# Snickerdoodle_PS.net
KiCad netlist of a schematic drawn in Altium Designer
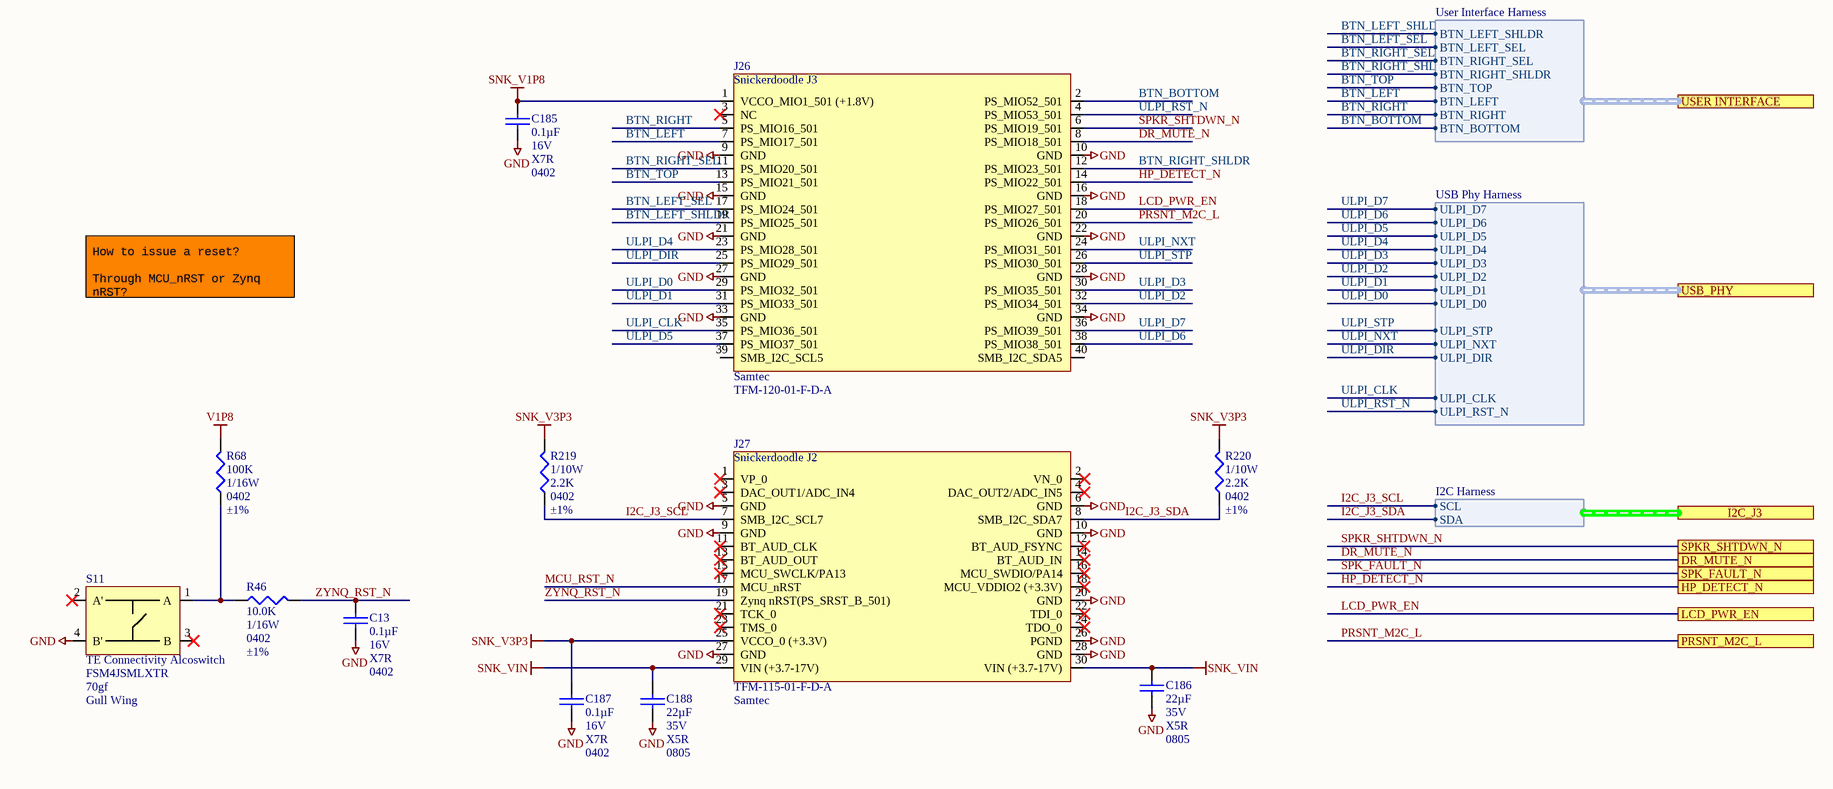
[diagram p0: Snickerdoodle PS.SchDoc]

(export (version "E")
  (design (tool "Eeschema 10.0.6"))
  (components
    (comp (ref "C13")
      (value "0.1uF")
      (footprint "C_0402")
      (description "CAP CER .10UF 16V X7R 0402")
      (fields
        (field (name "MANUFACTURER") "Murata Electronics North America")
        (field (name "MANUFACTURER PART NUMBER") "GRM155R71C104KA88J")
        (field (name "CAPACITANCE") "0.1µF")
        (field (name "VOLTAGE - RATED") "16V")
        (field (name "TEMPERATURE COEFFICIENT") "X7R")
        (field (name "PACKAGE / CASE") "0402")
      )
      (libsource (lib "Main LibraryX") (part "C_0402_0.1UF_16V"))
    )
    (comp (ref "C185")
      (value "0.1uF")
      (footprint "C_0402")
      (description "CAP CER .10UF 16V X7R 0402")
      (fields
        (field (name "MANUFACTURER") "Murata Electronics North America")
        (field (name "MANUFACTURER PART NUMBER") "GRM155R71C104KA88J")
        (field (name "CAPACITANCE") "0.1µF")
        (field (name "VOLTAGE - RATED") "16V")
        (field (name "TEMPERATURE COEFFICIENT") "X7R")
        (field (name "PACKAGE / CASE") "0402")
      )
      (libsource (lib "Main LibraryX") (part "C_0402_0.1UF_16V"))
    )
    (comp (ref "C186")
      (value "C_0805_22µF_35V")
      (footprint "C_ERA-0805")
      (description "CAP CER 22UF 35V X5R 0805")
      (fields
        (field (name "MANUFACTURER") "TDK Corporation")
        (field (name "MANUFACTURER PART NUMBER") "C2012X5R1V226M125AC")
        (field (name "CAPACITANCE") "22µF")
        (field (name "VOLTAGE - RATED") "35V")
        (field (name "TEMPERATURE COEFFICIENT") "X5R")
        (field (name "PACKAGE / CASE") "0805")
      )
      (libsource (lib "Cospan Design") (part "C_0805_22µF_35V"))
    )
    (comp (ref "C187")
      (value "0.1uF")
      (footprint "C_0402")
      (description "CAP CER .10UF 16V X7R 0402")
      (fields
        (field (name "MANUFACTURER") "Murata Electronics North America")
        (field (name "MANUFACTURER PART NUMBER") "GRM155R71C104KA88J")
        (field (name "CAPACITANCE") "0.1µF")
        (field (name "VOLTAGE - RATED") "16V")
        (field (name "TEMPERATURE COEFFICIENT") "X7R")
        (field (name "PACKAGE / CASE") "0402")
      )
      (libsource (lib "Main LibraryX") (part "C_0402_0.1UF_16V"))
    )
    (comp (ref "C188")
      (value "C_0805_22µF_35V")
      (footprint "C_ERA-0805")
      (description "CAP CER 22UF 35V X5R 0805")
      (fields
        (field (name "MANUFACTURER") "TDK Corporation")
        (field (name "MANUFACTURER PART NUMBER") "C2012X5R1V226M125AC")
        (field (name "CAPACITANCE") "22µF")
        (field (name "VOLTAGE - RATED") "35V")
        (field (name "TEMPERATURE COEFFICIENT") "X5R")
        (field (name "PACKAGE / CASE") "0805")
      )
      (libsource (lib "Cospan Design") (part "C_0805_22µF_35V"))
    )
    (comp (ref "J26")
      (value "J_SNICKERDOODLE_J3")
      (footprint "TFM12001-X-D-A")
      (description "SNICKERDOODLE J3")
      (fields
        (field (name "MANUFACTURER") "Samtec")
        (field (name "MANUFACTURER PART NUMBER") "TFM-120-01-F-D-A")
      )
      (libsource (lib "Cospan Design") (part "J_SNICKERDOODLE_J3"))
    )
    (comp (ref "J27")
      (value "J_SNICKERDOODLE_J2")
      (footprint "TFM11501-X-D-A")
      (description "SNICKERDOODLE J2")
      (fields
        (field (name "MANUFACTURER PART NUMBER") "TFM-115-01-F-D-A")
        (field (name "MANUFACTURER") "Samtec")
      )
      (libsource (lib "Cospan Design") (part "J_SNICKERDOODLE_J2"))
    )
    (comp (ref "R46")
      (value "R_0402_10.0K")
      (footprint "R_0402")
      (description "RES 10.0K OHM 1/16W 1% 0402 SMD")
      (fields
        (field (name "MANUFACTURER") "Stackpole Electronics Inc")
        (field (name "MANUFACTURER PART NUMBER") "RMCF0402FT10K0")
        (field (name "RESISTANCE IN OHMS") "10.0K")
        (field (name "POWER (WATTS)") "1/16W")
        (field (name "CASE") "0402")
        (field (name "TOLERANCE") "±1%")
      )
      (libsource (lib "Cospan Design") (part "R_0402_10.0K"))
    )
    (comp (ref "R68")
      (value "R_0402_100K")
      (footprint "R_0402")
      (description "RES SMD 100K OHM 1% 1/16W 0402")
      (fields
        (field (name "MANUFACTURER") "Yageo")
        (field (name "MANUFACTURER PART NUMBER") "RC0402FR-07100KL")
        (field (name "RESISTANCE IN OHMS") "100K")
        (field (name "POWER (WATTS)") "1/16W")
        (field (name "CASE") "0402")
        (field (name "TOLERANCE") "±1%")
      )
      (libsource (lib "Cospan Design") (part "R_0402_100K"))
    )
    (comp (ref "R219")
      (value "2.2k Ohms")
      (footprint "R_0402")
      (description "RES 2.20K OHM 1/10W 1% 0402 SMD")
      (fields
        (field (name "MANUFACTURER") "Yageo")
        (field (name "MANUFACTURER PART NUMBER") "RC0402FR-072K2L")
        (field (name "POWER (WATTS)") "1/10W")
        (field (name "RESISTANCE IN OHMS") "2.2K")
        (field (name "CASE") "0402")
        (field (name "TOLERANCE") "±1%")
      )
      (libsource (lib "Main Library") (part "R_0402_2.2K"))
    )
    (comp (ref "R220")
      (value "2.2k Ohms")
      (footprint "R_0402")
      (description "RES 2.20K OHM 1/10W 1% 0402 SMD")
      (fields
        (field (name "MANUFACTURER") "Yageo")
        (field (name "MANUFACTURER PART NUMBER") "RC0402FR-072K2L")
        (field (name "POWER (WATTS)") "1/10W")
        (field (name "RESISTANCE IN OHMS") "2.2K")
        (field (name "CASE") "0402")
        (field (name "TOLERANCE") "±1%")
      )
      (libsource (lib "Main Library") (part "R_0402_2.2K"))
    )
    (comp (ref "S11")
      (value "S_TACTILE_1571563_2_BUTTON")
      (footprint "TACTILE_1571563_2")
      (description "SWITCH TACTILE SPST-NO 0.05A 24V")
      (fields
        (field (name "MANUFACTURER") "TE Connectivity Alcoswitch")
        (field (name "MANUFACTURER PART NUMBER") "FSM4JSMLXTR")
        (field (name "OPERATING FORCE") "70gf")
        (field (name "TERMINATION") "Gull Wing")
      )
      (libsource (lib "Cospan Design") (part "S_TACTILE_1571563_2_BUTTON"))
    )
  )
  (nets
    (net (code "7") (name "/BTN_BOTTOM") (class "Default")
      (node (ref "J26") (pin "2") (pinfunction "PS_MIO52_501_2") (pintype "passive"))
    )
    (net (code "8") (name "/BTN_LEFT") (class "Default")
      (node (ref "J26") (pin "7") (pinfunction "PS_MIO17_501_7") (pintype "passive"))
    )
    (net (code "9") (name "/BTN_LEFT_SEL") (class "Default")
      (node (ref "J26") (pin "17") (pinfunction "PS_MIO24_501_17") (pintype "passive"))
    )
    (net (code "10") (name "/BTN_LEFT_SHLDR") (class "Default")
      (node (ref "J26") (pin "19") (pinfunction "PS_MIO25_501_19") (pintype "passive"))
    )
    (net (code "11") (name "/BTN_RIGHT") (class "Default")
      (node (ref "J26") (pin "5") (pinfunction "PS_MIO16_501_5") (pintype "passive"))
    )
    (net (code "12") (name "/BTN_RIGHT_SEL") (class "Default")
      (node (ref "J26") (pin "11") (pinfunction "PS_MIO20_501_11") (pintype "passive"))
    )
    (net (code "13") (name "/BTN_RIGHT_SHLDR") (class "Default")
      (node (ref "J26") (pin "12") (pinfunction "PS_MIO23_501_12") (pintype "passive"))
    )
    (net (code "14") (name "/BTN_TOP") (class "Default")
      (node (ref "J26") (pin "13") (pinfunction "PS_MIO21_501_13") (pintype "passive"))
    )
    (net (code "15") (name "/DR_MUTE_N") (class "Default")
      (node (ref "J26") (pin "8") (pinfunction "PS_MIO18_501_8") (pintype "passive"))
    )
    (net (code "16") (name "/HP_DETECT_N") (class "Default")
      (node (ref "J26") (pin "14") (pinfunction "PS_MIO22_501_14") (pintype "passive"))
    )
    (net (code "17") (name "/I2C_J3_SCL") (class "Default")
      (node (ref "J27") (pin "7") (pinfunction "SMB_I2C_SCL7_7") (pintype "passive"))
      (node (ref "R219") (pin "2") (pinfunction "2_2") (pintype "passive"))
    )
    (net (code "18") (name "/I2C_J3_SDA") (class "Default")
      (node (ref "J27") (pin "8") (pinfunction "SMB_I2C_SDA7_8") (pintype "passive"))
      (node (ref "R220") (pin "2") (pinfunction "2_2") (pintype "passive"))
    )
    (net (code "19") (name "/LCD_PWR_EN") (class "Default")
      (node (ref "J26") (pin "18") (pinfunction "PS_MIO27_501_18") (pintype "passive"))
    )
    (net (code "20") (name "/MCU_RST_N") (class "Default")
      (node (ref "J27") (pin "17") (pinfunction "MCU_nRST_17") (pintype "passive"))
    )
    (net (code "21") (name "/PRSNT_M2C_L") (class "Default")
      (node (ref "J26") (pin "20") (pinfunction "PS_MIO26_501_20") (pintype "passive"))
    )
    (net (code "22") (name "/SPKR_SHTDWN_N") (class "Default")
      (node (ref "J26") (pin "6") (pinfunction "PS_MIO19_501_6") (pintype "passive"))
    )
    (net (code "24") (name "/ULPI_CLK") (class "Default")
      (node (ref "J26") (pin "35") (pinfunction "PS_MIO36_501_35") (pintype "passive"))
    )
    (net (code "25") (name "/ULPI_D0") (class "Default")
      (node (ref "J26") (pin "29") (pinfunction "PS_MIO32_501_29") (pintype "passive"))
    )
    (net (code "26") (name "/ULPI_D1") (class "Default")
      (node (ref "J26") (pin "31") (pinfunction "PS_MIO33_501_31") (pintype "passive"))
    )
    (net (code "27") (name "/ULPI_D2") (class "Default")
      (node (ref "J26") (pin "32") (pinfunction "PS_MIO34_501_32") (pintype "passive"))
    )
    (net (code "28") (name "/ULPI_D3") (class "Default")
      (node (ref "J26") (pin "30") (pinfunction "PS_MIO35_501_30") (pintype "passive"))
    )
    (net (code "29") (name "/ULPI_D4") (class "Default")
      (node (ref "J26") (pin "23") (pinfunction "PS_MIO28_501_23") (pintype "passive"))
    )
    (net (code "30") (name "/ULPI_D5") (class "Default")
      (node (ref "J26") (pin "37") (pinfunction "PS_MIO37_501_37") (pintype "passive"))
    )
    (net (code "31") (name "/ULPI_D6") (class "Default")
      (node (ref "J26") (pin "38") (pinfunction "PS_MIO38_501_38") (pintype "passive"))
    )
    (net (code "32") (name "/ULPI_D7") (class "Default")
      (node (ref "J26") (pin "36") (pinfunction "PS_MIO39_501_36") (pintype "passive"))
    )
    (net (code "33") (name "/ULPI_DIR") (class "Default")
      (node (ref "J26") (pin "25") (pinfunction "PS_MIO29_501_25") (pintype "passive"))
    )
    (net (code "34") (name "/ULPI_NXT") (class "Default")
      (node (ref "J26") (pin "24") (pinfunction "PS_MIO31_501_24") (pintype "passive"))
    )
    (net (code "35") (name "/ULPI_RST_N") (class "Default")
      (node (ref "J26") (pin "4") (pinfunction "PS_MIO53_501_4") (pintype "passive"))
    )
    (net (code "36") (name "/ULPI_STP") (class "Default")
      (node (ref "J26") (pin "26") (pinfunction "PS_MIO30_501_26") (pintype "passive"))
    )
    (net (code "37") (name "/ZYNQ_RST_N") (class "Default")
      (node (ref "C13") (pin "2") (pinfunction "2_2") (pintype "passive"))
      (node (ref "J27") (pin "19") (pinfunction "Zynq_nRST(PS_SRST_B_501)_19") (pintype "passive"))
      (node (ref "R46") (pin "1") (pinfunction "1_1") (pintype "passive"))
    )
    (net (code "41") (name "GND") (class "Default")
      (node (ref "C13") (pin "1") (pinfunction "1_1") (pintype "passive"))
      (node (ref "C185") (pin "1") (pinfunction "1_1") (pintype "passive"))
      (node (ref "C186") (pin "1") (pinfunction "1_1") (pintype "passive"))
      (node (ref "C187") (pin "1") (pinfunction "1_1") (pintype "passive"))
      (node (ref "C188") (pin "1") (pinfunction "1_1") (pintype "passive"))
      (node (ref "J26") (pin "10") (pinfunction "GND_10") (pintype "passive"))
      (node (ref "J26") (pin "15") (pinfunction "GND_15") (pintype "passive"))
      (node (ref "J26") (pin "16") (pinfunction "GND_16") (pintype "passive"))
      (node (ref "J26") (pin "21") (pinfunction "GND_21") (pintype "passive"))
      (node (ref "J26") (pin "22") (pinfunction "GND_22") (pintype "passive"))
      (node (ref "J26") (pin "27") (pinfunction "GND_27") (pintype "passive"))
      (node (ref "J26") (pin "28") (pinfunction "GND_28") (pintype "passive"))
      (node (ref "J26") (pin "33") (pinfunction "GND_33") (pintype "passive"))
      (node (ref "J26") (pin "34") (pinfunction "GND_34") (pintype "passive"))
      (node (ref "J26") (pin "9") (pinfunction "GND_9") (pintype "passive"))
      (node (ref "J27") (pin "10") (pinfunction "GND_10") (pintype "passive"))
      (node (ref "J27") (pin "20") (pinfunction "GND_20") (pintype "passive"))
      (node (ref "J27") (pin "26") (pinfunction "PGND_26") (pintype "passive"))
      (node (ref "J27") (pin "27") (pinfunction "GND_27") (pintype "passive"))
      (node (ref "J27") (pin "28") (pinfunction "GND_28") (pintype "passive"))
      (node (ref "J27") (pin "5") (pinfunction "GND_5") (pintype "passive"))
      (node (ref "J27") (pin "6") (pinfunction "GND_6") (pintype "passive"))
      (node (ref "J27") (pin "9") (pinfunction "GND_9") (pintype "passive"))
      (node (ref "S11") (pin "4") (pinfunction "B'_4") (pintype "passive"))
    )
    (net (code "42") (name "Net-(S11-A)") (class "Default")
      (node (ref "R46") (pin "2") (pinfunction "2_2") (pintype "passive"))
      (node (ref "R68") (pin "2") (pinfunction "2_2") (pintype "passive"))
      (node (ref "S11") (pin "1") (pinfunction "A_1") (pintype "passive"))
    )
    (net (code "43") (name "SNK_V1P8") (class "Default")
      (node (ref "C185") (pin "2") (pinfunction "2_2") (pintype "passive"))
      (node (ref "J26") (pin "1") (pinfunction "VCCO_MIO1_501_(+1.8V)_1") (pintype "passive"))
    )
    (net (code "44") (name "SNK_V3P3") (class "Default")
      (node (ref "C187") (pin "2") (pinfunction "2_2") (pintype "passive"))
      (node (ref "J27") (pin "25") (pinfunction "VCCO_0_(+3.3V)_25") (pintype "passive"))
      (node (ref "R219") (pin "1") (pinfunction "1_1") (pintype "passive"))
      (node (ref "R220") (pin "1") (pinfunction "1_1") (pintype "passive"))
    )
    (net (code "45") (name "SNK_VIN") (class "Default")
      (node (ref "C186") (pin "2") (pinfunction "2_2") (pintype "passive"))
      (node (ref "C188") (pin "2") (pinfunction "2_2") (pintype "passive"))
      (node (ref "J27") (pin "29") (pinfunction "VIN_(+3.7-17V)_29") (pintype "passive"))
      (node (ref "J27") (pin "30") (pinfunction "VIN_(+3.7-17V)_30") (pintype "passive"))
    )
    (net (code "46") (name "V1P8") (class "Default")
      (node (ref "R68") (pin "1") (pinfunction "1_1") (pintype "passive"))
    )
    (net (code "47") (name "unconnected-(J26-NC-Pad3)") (class "Default")
      (node (ref "J26") (pin "3") (pinfunction "NC_3") (pintype "passive+no_connect"))
    )
    (net (code "48") (name "unconnected-(J26-SMB_I2C_SCL5-Pad39)") (class "Default")
      (node (ref "J26") (pin "39") (pinfunction "SMB_I2C_SCL5_39") (pintype "passive"))
    )
    (net (code "49") (name "unconnected-(J26-SMB_I2C_SDA5-Pad40)") (class "Default")
      (node (ref "J26") (pin "40") (pinfunction "SMB_I2C_SDA5_40") (pintype "passive"))
    )
    (net (code "50") (name "unconnected-(J27-BT_AUD_CLK-Pad11)") (class "Default")
      (node (ref "J27") (pin "11") (pinfunction "BT_AUD_CLK_11") (pintype "passive+no_connect"))
    )
    (net (code "51") (name "unconnected-(J27-BT_AUD_FSYNC-Pad12)") (class "Default")
      (node (ref "J27") (pin "12") (pinfunction "BT_AUD_FSYNC_12") (pintype "passive+no_connect"))
    )
    (net (code "52") (name "unconnected-(J27-BT_AUD_IN-Pad14)") (class "Default")
      (node (ref "J27") (pin "14") (pinfunction "BT_AUD_IN_14") (pintype "passive+no_connect"))
    )
    (net (code "53") (name "unconnected-(J27-BT_AUD_OUT-Pad13)") (class "Default")
      (node (ref "J27") (pin "13") (pinfunction "BT_AUD_OUT_13") (pintype "passive+no_connect"))
    )
    (net (code "54") (name "unconnected-(J27-DAC_OUT1{slash}ADC_IN4-Pad3)") (class "Default")
      (node (ref "J27") (pin "3") (pinfunction "DAC_OUT1/ADC_IN4_3") (pintype "passive+no_connect"))
    )
    (net (code "55") (name "unconnected-(J27-DAC_OUT2{slash}ADC_IN5-Pad4)") (class "Default")
      (node (ref "J27") (pin "4") (pinfunction "DAC_OUT2/ADC_IN5_4") (pintype "passive+no_connect"))
    )
    (net (code "56") (name "unconnected-(J27-MCU_SWCLK{slash}PA13-Pad15)") (class "Default")
      (node (ref "J27") (pin "15") (pinfunction "MCU_SWCLK/PA13_15") (pintype "passive+no_connect"))
    )
    (net (code "57") (name "unconnected-(J27-MCU_SWDIO{slash}PA14-Pad16)") (class "Default")
      (node (ref "J27") (pin "16") (pinfunction "MCU_SWDIO/PA14_16") (pintype "passive+no_connect"))
    )
    (net (code "58") (name "unconnected-(J27-MCU_VDDIO2_(+3.3V)-Pad18)") (class "Default")
      (node (ref "J27") (pin "18") (pinfunction "MCU_VDDIO2_(+3.3V)_18") (pintype "passive+no_connect"))
    )
    (net (code "59") (name "unconnected-(J27-TCK_0-Pad21)") (class "Default")
      (node (ref "J27") (pin "21") (pinfunction "TCK_0_21") (pintype "passive+no_connect"))
    )
    (net (code "60") (name "unconnected-(J27-TDI_0-Pad22)") (class "Default")
      (node (ref "J27") (pin "22") (pinfunction "TDI_0_22") (pintype "passive+no_connect"))
    )
    (net (code "61") (name "unconnected-(J27-TDO_0-Pad24)") (class "Default")
      (node (ref "J27") (pin "24") (pinfunction "TDO_0_24") (pintype "passive+no_connect"))
    )
    (net (code "62") (name "unconnected-(J27-TMS_0-Pad23)") (class "Default")
      (node (ref "J27") (pin "23") (pinfunction "TMS_0_23") (pintype "passive+no_connect"))
    )
    (net (code "63") (name "unconnected-(J27-VN_0-Pad2)") (class "Default")
      (node (ref "J27") (pin "2") (pinfunction "VN_0_2") (pintype "passive+no_connect"))
    )
    (net (code "64") (name "unconnected-(J27-VP_0-Pad1)") (class "Default")
      (node (ref "J27") (pin "1") (pinfunction "VP_0_1") (pintype "passive+no_connect"))
    )
    (net (code "65") (name "unconnected-(S11-A'-Pad2)") (class "Default")
      (node (ref "S11") (pin "2") (pinfunction "A'_2") (pintype "passive+no_connect"))
    )
    (net (code "66") (name "unconnected-(S11-B-Pad3)") (class "Default")
      (node (ref "S11") (pin "3") (pinfunction "B_3") (pintype "passive+no_connect"))
    )
  )
)
